# SparkFun-LSM9DS1-Breakout.net
KiCad netlist of a schematic drawn in EAGLE
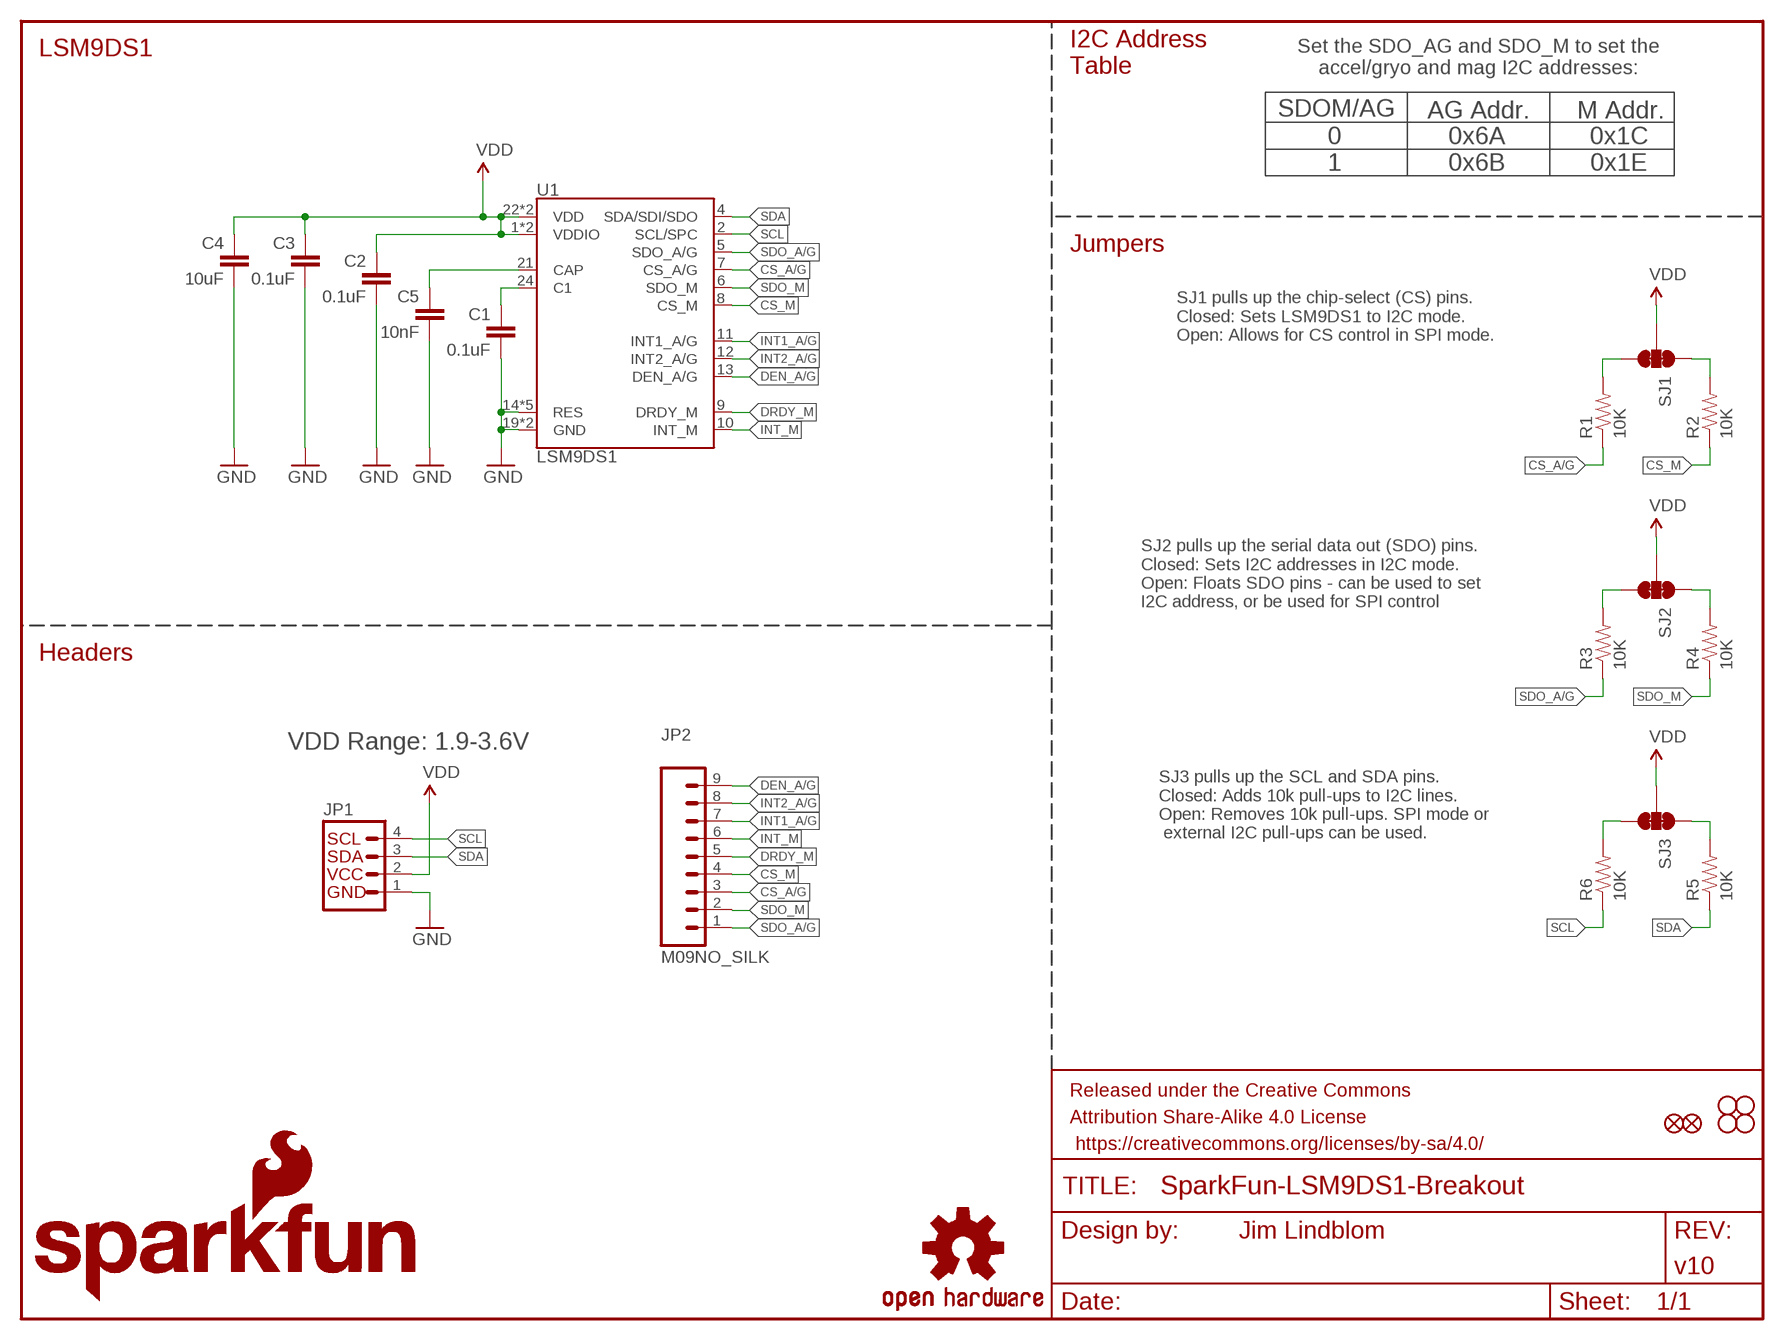
[diagram p0: schematic, sheet 1]

(export (version "E")
  (design (tool "Eeschema 10.0.6"))
  (components
    (comp (ref "C1")
      (value "0.1uF")
      (footprint "eagle-import:0603-CAP")
      (libsource (lib "eagle-import") (part "0.1UF-25V(+80/-20%)(0603)"))
    )
    (comp (ref "C2")
      (value "0.1uF")
      (footprint "eagle-import:0603-CAP")
      (libsource (lib "eagle-import") (part "0.1UF-25V(+80/-20%)(0603)"))
    )
    (comp (ref "C3")
      (value "0.1uF")
      (footprint "eagle-import:0603-CAP")
      (libsource (lib "eagle-import") (part "0.1UF-25V(+80/-20%)(0603)"))
    )
    (comp (ref "C4")
      (value "10uF")
      (footprint "eagle-import:0603-CAP")
      (libsource (lib "eagle-import") (part "10UF-6.3V-20%(0603)"))
    )
    (comp (ref "C5")
      (value "10nF")
      (footprint "eagle-import:0603-CAP")
      (libsource (lib "eagle-import") (part "10NF/10000PF-50V-10%(0603)"))
    )
    (comp (ref "FID1")
      (value "FIDUCIAL1X2")
      (footprint "eagle-import:FIDUCIAL-1X2")
      (libsource (lib "eagle-import") (part "FIDUCIAL1X2"))
    )
    (comp (ref "FID2")
      (value "FIDUCIAL1X2")
      (footprint "eagle-import:FIDUCIAL-1X2")
      (libsource (lib "eagle-import") (part "FIDUCIAL1X2"))
    )
    (comp (ref "FRAME1")
      (value "FRAME-LETTER")
      (footprint "eagle-import:CREATIVE_COMMONS")
      (fields (field (name "DESIGNER") "Jim Lindblom") (field (name "VERSION") "v10"))
      (libsource (lib "eagle-import") (part "FRAME-LETTER"))
    )
    (comp (ref "JP1")
      (value "I2C_STANDARD_NO_SILK")
      (footprint "eagle-import:1X04_NO_SILK")
      (libsource (lib "eagle-import") (part "I2C_STANDARD_NO_SILK"))
    )
    (comp (ref "JP2")
      (value "M09NO_SILK")
      (footprint "eagle-import:1X09_NO_SILK")
      (libsource (lib "eagle-import") (part "M09NO_SILK"))
    )
    (comp (ref "LOGO1")
      (value "SFE_LOGO_NAME.1_INCH")
      (footprint "eagle-import:SFE_LOGO_NAME_.1")
      (libsource (lib "eagle-import") (part "SFE_LOGO_NAME.1_INCH"))
    )
    (comp (ref "LOGO2")
      (value "SFE_LOGO_FLAME.2_INCH")
      (footprint "eagle-import:SFE_LOGO_FLAME_.2")
      (libsource (lib "eagle-import") (part "SFE_LOGO_FLAME.2_INCH"))
    )
    (comp (ref "LOGO3")
      (value "OSHW-LOGOS")
      (footprint "eagle-import:OSHW-LOGO-S")
      (libsource (lib "eagle-import") (part "OSHW-LOGOS"))
    )
    (comp (ref "R1")
      (value "10K")
      (footprint "eagle-import:0603-RES")
      (libsource (lib "eagle-import") (part "10KOHM-1/10W-1%(0603)0603"))
    )
    (comp (ref "R2")
      (value "10K")
      (footprint "eagle-import:0603-RES")
      (libsource (lib "eagle-import") (part "10KOHM-1/10W-1%(0603)0603"))
    )
    (comp (ref "R3")
      (value "10K")
      (footprint "eagle-import:0603-RES")
      (libsource (lib "eagle-import") (part "10KOHM-1/10W-1%(0603)0603"))
    )
    (comp (ref "R4")
      (value "10K")
      (footprint "eagle-import:0603-RES")
      (libsource (lib "eagle-import") (part "10KOHM-1/10W-1%(0603)0603"))
    )
    (comp (ref "R5")
      (value "10K")
      (footprint "eagle-import:0603-RES")
      (libsource (lib "eagle-import") (part "10KOHM-1/10W-1%(0603)0603"))
    )
    (comp (ref "R6")
      (value "10K")
      (footprint "eagle-import:0603-RES")
      (libsource (lib "eagle-import") (part "10KOHM-1/10W-1%(0603)0603"))
    )
    (comp (ref "SJ1")
      (value "JUMPER-PAD-3-NC_BY_TRACE")
      (footprint "eagle-import:PAD-JUMPER-3-3OF3_NC_BY_TRACE_YES_SILK_FULL_BOX")
      (libsource (lib "eagle-import") (part "JUMPER-PAD-3-NC_BY_TRACE"))
    )
    (comp (ref "SJ2")
      (value "JUMPER-PAD-3-NC_BY_TRACE")
      (footprint "eagle-import:PAD-JUMPER-3-3OF3_NC_BY_TRACE_YES_SILK_FULL_BOX")
      (libsource (lib "eagle-import") (part "JUMPER-PAD-3-NC_BY_TRACE"))
    )
    (comp (ref "SJ3")
      (value "JUMPER-PAD-3-NC_BY_TRACE")
      (footprint "eagle-import:PAD-JUMPER-3-3OF3_NC_BY_TRACE_YES_SILK_FULL_BOX")
      (libsource (lib "eagle-import") (part "JUMPER-PAD-3-NC_BY_TRACE"))
    )
    (comp (ref "STANDOFF1")
      (value "STAND-OFF")
      (footprint "eagle-import:STAND-OFF")
      (libsource (lib "eagle-import") (part "STAND-OFF"))
    )
    (comp (ref "STANDOFF2")
      (value "STAND-OFF")
      (footprint "eagle-import:STAND-OFF")
      (libsource (lib "eagle-import") (part "STAND-OFF"))
    )
    (comp (ref "STANDOFF3")
      (value "STAND-OFF")
      (footprint "eagle-import:STAND-OFF")
      (libsource (lib "eagle-import") (part "STAND-OFF"))
    )
    (comp (ref "STANDOFF4")
      (value "STAND-OFF")
      (footprint "eagle-import:STAND-OFF")
      (libsource (lib "eagle-import") (part "STAND-OFF"))
    )
    (comp (ref "U1")
      (value "LSM9DS1")
      (footprint "eagle-import:LGA24-8X4")
      (libsource (lib "eagle-import") (part "LSM9DS1"))
    )
  )
  (nets
    (net (code "1") (name "CS_A{slash}G") (class "Default")
      (node (ref "JP2") (pin "3") (pinfunction "3_3") (pintype "passive"))
      (node (ref "R1") (pin "1") (pinfunction "1_1") (pintype "passive"))
      (node (ref "U1") (pin "7") (pinfunction "CS_A/G_7") (pintype "bidirectional"))
    )
    (net (code "2") (name "CS_M") (class "Default")
      (node (ref "JP2") (pin "4") (pinfunction "4_4") (pintype "passive"))
      (node (ref "R2") (pin "1") (pinfunction "1_1") (pintype "passive"))
      (node (ref "U1") (pin "8") (pinfunction "CS_M_8") (pintype "bidirectional"))
    )
    (net (code "3") (name "DEN_A{slash}G") (class "Default")
      (node (ref "JP2") (pin "9") (pinfunction "9_9") (pintype "passive"))
      (node (ref "U1") (pin "13") (pinfunction "DEN_A/G_13") (pintype "bidirectional"))
    )
    (net (code "4") (name "DRDY_M") (class "Default")
      (node (ref "JP2") (pin "5") (pinfunction "5_5") (pintype "passive"))
      (node (ref "U1") (pin "9") (pinfunction "DRDY_M_9") (pintype "bidirectional"))
    )
    (net (code "5") (name "GND") (class "Default")
      (node (ref "C1") (pin "2") (pinfunction "2_2") (pintype "passive"))
      (node (ref "C2") (pin "2") (pinfunction "2_2") (pintype "passive"))
      (node (ref "C3") (pin "2") (pinfunction "2_2") (pintype "passive"))
      (node (ref "C4") (pin "2") (pinfunction "2_2") (pintype "passive"))
      (node (ref "C5") (pin "2") (pinfunction "2_2") (pintype "passive"))
      (node (ref "JP1") (pin "1") (pinfunction "1_1") (pintype "passive"))
      (node (ref "U1") (pin "14") (pinfunction "RES_14") (pintype "bidirectional"))
      (node (ref "U1") (pin "15") (pinfunction "RES_15") (pintype "bidirectional"))
      (node (ref "U1") (pin "16") (pinfunction "RES_16") (pintype "bidirectional"))
      (node (ref "U1") (pin "17") (pinfunction "RES_17") (pintype "bidirectional"))
      (node (ref "U1") (pin "18") (pinfunction "RES_18") (pintype "bidirectional"))
      (node (ref "U1") (pin "19") (pinfunction "GND_19") (pintype "bidirectional"))
      (node (ref "U1") (pin "20") (pinfunction "GND_20") (pintype "bidirectional"))
    )
    (net (code "6") (name "INT1_A{slash}G") (class "Default")
      (node (ref "JP2") (pin "7") (pinfunction "7_7") (pintype "passive"))
      (node (ref "U1") (pin "11") (pinfunction "INT1_A/G_11") (pintype "bidirectional"))
    )
    (net (code "7") (name "INT2_A{slash}G") (class "Default")
      (node (ref "JP2") (pin "8") (pinfunction "8_8") (pintype "passive"))
      (node (ref "U1") (pin "12") (pinfunction "INT2_A/G_12") (pintype "bidirectional"))
    )
    (net (code "8") (name "INT_M") (class "Default")
      (node (ref "JP2") (pin "6") (pinfunction "6_6") (pintype "passive"))
      (node (ref "U1") (pin "10") (pinfunction "INT_M_10") (pintype "bidirectional"))
    )
    (net (code "9") (name "Net-(R1-Pad2)") (class "Default")
      (node (ref "R1") (pin "2") (pinfunction "2_2") (pintype "passive"))
      (node (ref "SJ1") (pin "3") (pinfunction "3_3") (pintype "passive"))
    )
    (net (code "10") (name "Net-(R2-Pad2)") (class "Default")
      (node (ref "R2") (pin "2") (pinfunction "2_2") (pintype "passive"))
      (node (ref "SJ1") (pin "1") (pinfunction "1_1") (pintype "passive"))
    )
    (net (code "11") (name "Net-(R3-Pad2)") (class "Default")
      (node (ref "R3") (pin "2") (pinfunction "2_2") (pintype "passive"))
      (node (ref "SJ2") (pin "3") (pinfunction "3_3") (pintype "passive"))
    )
    (net (code "12") (name "Net-(R4-Pad2)") (class "Default")
      (node (ref "R4") (pin "2") (pinfunction "2_2") (pintype "passive"))
      (node (ref "SJ2") (pin "1") (pinfunction "1_1") (pintype "passive"))
    )
    (net (code "13") (name "Net-(R5-Pad2)") (class "Default")
      (node (ref "R5") (pin "2") (pinfunction "2_2") (pintype "passive"))
      (node (ref "SJ3") (pin "1") (pinfunction "1_1") (pintype "passive"))
    )
    (net (code "14") (name "Net-(R6-Pad2)") (class "Default")
      (node (ref "R6") (pin "2") (pinfunction "2_2") (pintype "passive"))
      (node (ref "SJ3") (pin "3") (pinfunction "3_3") (pintype "passive"))
    )
    (net (code "15") (name "Net-(U1-C1)") (class "Default")
      (node (ref "C1") (pin "1") (pinfunction "1_1") (pintype "passive"))
      (node (ref "U1") (pin "24") (pinfunction "C1_24") (pintype "bidirectional"))
    )
    (net (code "16") (name "Net-(U1-CAP)") (class "Default")
      (node (ref "C5") (pin "1") (pinfunction "1_1") (pintype "passive"))
      (node (ref "U1") (pin "21") (pinfunction "CAP_21") (pintype "bidirectional"))
    )
    (net (code "17") (name "SCL") (class "Default")
      (node (ref "JP1") (pin "4") (pinfunction "4_4") (pintype "passive"))
      (node (ref "R6") (pin "1") (pinfunction "1_1") (pintype "passive"))
      (node (ref "U1") (pin "2") (pinfunction "SCL/SPC_2") (pintype "bidirectional"))
    )
    (net (code "18") (name "SDA") (class "Default")
      (node (ref "JP1") (pin "3") (pinfunction "3_3") (pintype "passive"))
      (node (ref "R5") (pin "1") (pinfunction "1_1") (pintype "passive"))
      (node (ref "U1") (pin "4") (pinfunction "SDA/SDI/SDO_4") (pintype "bidirectional"))
    )
    (net (code "19") (name "SDO_A{slash}G") (class "Default")
      (node (ref "JP2") (pin "1") (pinfunction "1_1") (pintype "passive"))
      (node (ref "R3") (pin "1") (pinfunction "1_1") (pintype "passive"))
      (node (ref "U1") (pin "5") (pinfunction "SDO_A/G_5") (pintype "bidirectional"))
    )
    (net (code "20") (name "SDO_M") (class "Default")
      (node (ref "JP2") (pin "2") (pinfunction "2_2") (pintype "passive"))
      (node (ref "R4") (pin "1") (pinfunction "1_1") (pintype "passive"))
      (node (ref "U1") (pin "6") (pinfunction "SDO_M_6") (pintype "bidirectional"))
    )
    (net (code "21") (name "VDD") (class "Default")
      (node (ref "C2") (pin "1") (pinfunction "1_1") (pintype "passive"))
      (node (ref "C3") (pin "1") (pinfunction "1_1") (pintype "passive"))
      (node (ref "C4") (pin "1") (pinfunction "1_1") (pintype "passive"))
      (node (ref "JP1") (pin "2") (pinfunction "2_2") (pintype "passive"))
      (node (ref "SJ1") (pin "2") (pinfunction "2_2") (pintype "passive"))
      (node (ref "SJ2") (pin "2") (pinfunction "2_2") (pintype "passive"))
      (node (ref "SJ3") (pin "2") (pinfunction "2_2") (pintype "passive"))
      (node (ref "U1") (pin "1") (pinfunction "VDDIO_1") (pintype "bidirectional"))
      (node (ref "U1") (pin "22") (pinfunction "VDD_22") (pintype "bidirectional"))
      (node (ref "U1") (pin "23") (pinfunction "VDD_23") (pintype "bidirectional"))
      (node (ref "U1") (pin "3") (pinfunction "VDDIO_3") (pintype "bidirectional"))
    )
  )
)
